# BMD_RevB_B3_FPGA.net
KiCad netlist of a schematic drawn in Altium Designer
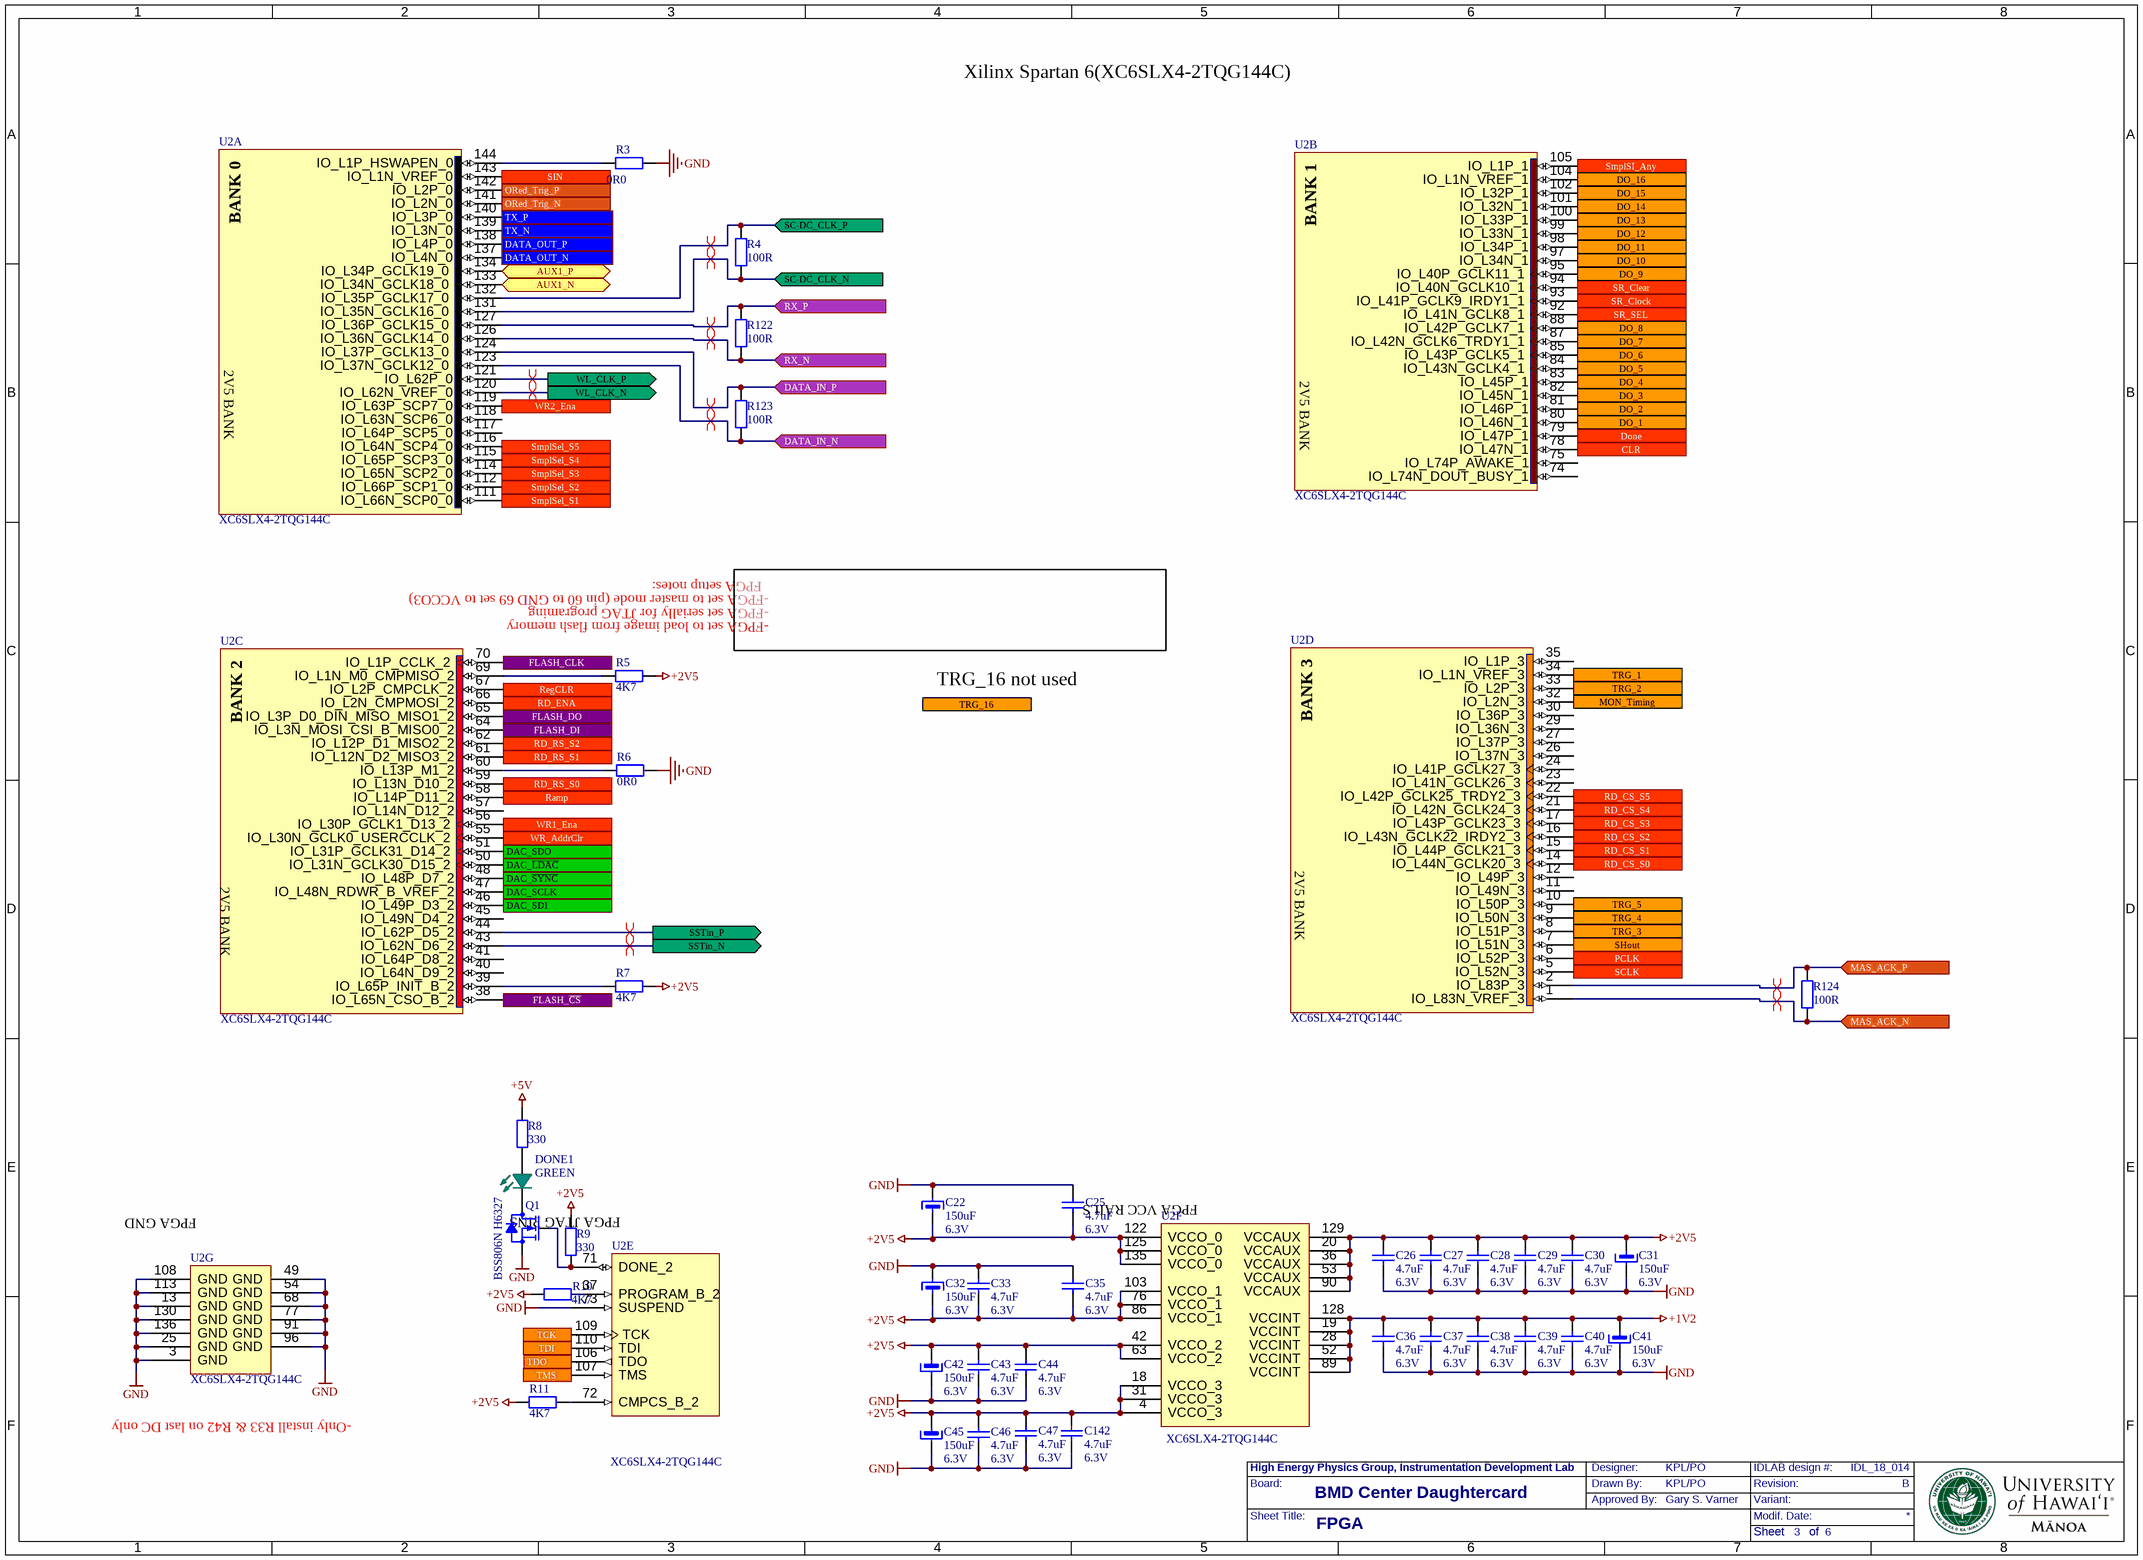
[diagram p0: BMD_RevB_B3_FPGA.SchDoc]

(export (version "E")
  (design (tool "Eeschema 10.0.6"))
  (components
    (comp (ref "C22")
      (value "150uF")
      (footprint "CTC-B3528-21")
      (description "150µF Molded Tantalum Capacitors 6.3V 1411")
      (fields (field (name "MANUFACTURER") "AVX") (field (name "VOLTAGE") "6.3V"))
      (libsource (lib "") (part "CAPT3528_150U6V3R0.5_1"))
    )
    (comp (ref "C25")
      (value "4.7uF")
      (footprint "CC0402N1R")
      (description "4.7µF ±10% 6.3V X7R Ceramic Capacitor")
      (fields
        (field (name "MANUFACTURER") "Samsung Electro-Mechanics America, Inc.")
        (field (name "VOLTAGE RATING") "6.3V")
      )
      (libsource (lib "BMD") (part "CAPCC0402_4.7uF_6.3V"))
    )
    (comp (ref "C26")
      (value "4.7uF")
      (footprint "CC0402N1R")
      (description "4.7µF ±10% 6.3V X7R Ceramic Capacitor")
      (fields
        (field (name "MANUFACTURER") "Samsung Electro-Mechanics America, Inc.")
        (field (name "VOLTAGE RATING") "6.3V")
      )
      (libsource (lib "BMD") (part "CAPCC0402_4.7uF_6.3V"))
    )
    (comp (ref "C27")
      (value "4.7uF")
      (footprint "CC0402N1R")
      (description "4.7µF ±10% 6.3V X7R Ceramic Capacitor")
      (fields
        (field (name "MANUFACTURER") "Samsung Electro-Mechanics America, Inc.")
        (field (name "VOLTAGE RATING") "6.3V")
      )
      (libsource (lib "BMD") (part "CAPCC0402_4.7uF_6.3V"))
    )
    (comp (ref "C28")
      (value "4.7uF")
      (footprint "CC0402N1R")
      (description "4.7µF ±10% 6.3V X7R Ceramic Capacitor")
      (fields
        (field (name "MANUFACTURER") "Samsung Electro-Mechanics America, Inc.")
        (field (name "VOLTAGE RATING") "6.3V")
      )
      (libsource (lib "BMD") (part "CAPCC0402_4.7uF_6.3V"))
    )
    (comp (ref "C29")
      (value "4.7uF")
      (footprint "CC0402N1R")
      (description "4.7µF ±10% 6.3V X7R Ceramic Capacitor")
      (fields
        (field (name "MANUFACTURER") "Samsung Electro-Mechanics America, Inc.")
        (field (name "VOLTAGE RATING") "6.3V")
      )
      (libsource (lib "BMD") (part "CAPCC0402_4.7uF_6.3V"))
    )
    (comp (ref "C30")
      (value "4.7uF")
      (footprint "CC0402N1R")
      (description "4.7µF ±10% 6.3V X7R Ceramic Capacitor")
      (fields
        (field (name "MANUFACTURER") "Samsung Electro-Mechanics America, Inc.")
        (field (name "VOLTAGE RATING") "6.3V")
      )
      (libsource (lib "BMD") (part "CAPCC0402_4.7uF_6.3V"))
    )
    (comp (ref "C31")
      (value "150uF")
      (footprint "CTC-B3528-21")
      (description "150µF Molded Tantalum Capacitors 6.3V 1411")
      (fields (field (name "MANUFACTURER") "AVX") (field (name "VOLTAGE") "6.3V"))
      (libsource (lib "BMD") (part "CAPT3528_150U6V3R0.5"))
    )
    (comp (ref "C32")
      (value "150uF")
      (footprint "CTC-B3528-21")
      (description "150µF Molded Tantalum Capacitors 6.3V 1411")
      (fields (field (name "MANUFACTURER") "AVX") (field (name "VOLTAGE") "6.3V"))
      (libsource (lib "") (part "CAPT3528_150U6V3R0.5_1"))
    )
    (comp (ref "C33")
      (value "4.7uF")
      (footprint "CC0402N1R")
      (description "4.7µF ±10% 6.3V X7R Ceramic Capacitor")
      (fields
        (field (name "MANUFACTURER") "Samsung Electro-Mechanics America, Inc.")
        (field (name "VOLTAGE RATING") "6.3V")
      )
      (libsource (lib "BMD") (part "CAPCC0402_4.7uF_6.3V"))
    )
    (comp (ref "C35")
      (value "4.7uF")
      (footprint "CC0402N1R")
      (description "4.7µF ±10% 6.3V X7R Ceramic Capacitor")
      (fields
        (field (name "MANUFACTURER") "Samsung Electro-Mechanics America, Inc.")
        (field (name "VOLTAGE RATING") "6.3V")
      )
      (libsource (lib "BMD") (part "CAPCC0402_4.7uF_6.3V"))
    )
    (comp (ref "C36")
      (value "4.7uF")
      (footprint "CC0402N1R")
      (description "4.7µF ±10% 6.3V X7R Ceramic Capacitor")
      (fields
        (field (name "MANUFACTURER") "Samsung Electro-Mechanics America, Inc.")
        (field (name "VOLTAGE RATING") "6.3V")
      )
      (libsource (lib "BMD") (part "CAPCC0402_4.7uF_6.3V"))
    )
    (comp (ref "C37")
      (value "4.7uF")
      (footprint "CC0402N1R")
      (description "4.7µF ±10% 6.3V X7R Ceramic Capacitor")
      (fields
        (field (name "MANUFACTURER") "Samsung Electro-Mechanics America, Inc.")
        (field (name "VOLTAGE RATING") "6.3V")
      )
      (libsource (lib "BMD") (part "CAPCC0402_4.7uF_6.3V"))
    )
    (comp (ref "C38")
      (value "4.7uF")
      (footprint "CC0402N1R")
      (description "4.7µF ±10% 6.3V X7R Ceramic Capacitor")
      (fields
        (field (name "MANUFACTURER") "Samsung Electro-Mechanics America, Inc.")
        (field (name "VOLTAGE RATING") "6.3V")
      )
      (libsource (lib "BMD") (part "CAPCC0402_4.7uF_6.3V"))
    )
    (comp (ref "C39")
      (value "4.7uF")
      (footprint "CC0402N1R")
      (description "4.7µF ±10% 6.3V X7R Ceramic Capacitor")
      (fields
        (field (name "MANUFACTURER") "Samsung Electro-Mechanics America, Inc.")
        (field (name "VOLTAGE RATING") "6.3V")
      )
      (libsource (lib "BMD") (part "CAPCC0402_4.7uF_6.3V"))
    )
    (comp (ref "C40")
      (value "4.7uF")
      (footprint "CC0402N1R")
      (description "4.7µF ±10% 6.3V X7R Ceramic Capacitor")
      (fields
        (field (name "MANUFACTURER") "Samsung Electro-Mechanics America, Inc.")
        (field (name "VOLTAGE RATING") "6.3V")
      )
      (libsource (lib "BMD") (part "CAPCC0402_4.7uF_6.3V"))
    )
    (comp (ref "C41")
      (value "150uF")
      (footprint "CTC-B3528-21")
      (description "150µF Molded Tantalum Capacitors 6.3V 1411")
      (fields (field (name "MANUFACTURER") "AVX") (field (name "VOLTAGE") "6.3V"))
      (libsource (lib "BMD") (part "CAPT3528_150U6V3R0.5"))
    )
    (comp (ref "C42")
      (value "150uF")
      (footprint "CTC-B3528-21")
      (description "150µF Molded Tantalum Capacitors 6.3V 1411")
      (fields (field (name "MANUFACTURER") "AVX") (field (name "VOLTAGE") "6.3V"))
      (libsource (lib "BMD") (part "CAPT3528_150U6V3R0.5"))
    )
    (comp (ref "C43")
      (value "4.7uF")
      (footprint "CC0402N1R")
      (description "4.7µF ±10% 6.3V X7R Ceramic Capacitor")
      (fields
        (field (name "MANUFACTURER") "Samsung Electro-Mechanics America, Inc.")
        (field (name "VOLTAGE RATING") "6.3V")
      )
      (libsource (lib "BMD") (part "CAPCC0402_4.7uF_6.3V"))
    )
    (comp (ref "C44")
      (value "4.7uF")
      (footprint "CC0402N1R")
      (description "4.7µF ±10% 6.3V X7R Ceramic Capacitor")
      (fields
        (field (name "MANUFACTURER") "Samsung Electro-Mechanics America, Inc.")
        (field (name "VOLTAGE RATING") "6.3V")
      )
      (libsource (lib "BMD") (part "CAPCC0402_4.7uF_6.3V"))
    )
    (comp (ref "C45")
      (value "150uF")
      (footprint "CTC-B3528-21")
      (description "150µF Molded Tantalum Capacitors 6.3V 1411")
      (fields (field (name "MANUFACTURER") "AVX") (field (name "VOLTAGE") "6.3V"))
      (libsource (lib "BMD") (part "CAPT3528_150U6V3R0.5"))
    )
    (comp (ref "C46")
      (value "4.7uF")
      (footprint "CC0402N1R")
      (description "4.7µF ±10% 6.3V X7R Ceramic Capacitor")
      (fields
        (field (name "MANUFACTURER") "Samsung Electro-Mechanics America, Inc.")
        (field (name "VOLTAGE RATING") "6.3V")
      )
      (libsource (lib "BMD") (part "CAPCC0402_4.7uF_6.3V"))
    )
    (comp (ref "C47")
      (value "4.7uF")
      (footprint "CC0402N1R")
      (description "4.7µF ±10% 6.3V X7R Ceramic Capacitor")
      (fields
        (field (name "MANUFACTURER") "Samsung Electro-Mechanics America, Inc.")
        (field (name "VOLTAGE RATING") "6.3V")
      )
      (libsource (lib "BMD") (part "CAPCC0402_4.7uF_6.3V"))
    )
    (comp (ref "C142")
      (value "4.7uF")
      (footprint "CC0402N1R")
      (description "4.7µF ±10% 6.3V X7R Ceramic Capacitor")
      (fields
        (field (name "MANUFACTURER") "Samsung Electro-Mechanics America, Inc.")
        (field (name "VOLTAGE RATING") "6.3V")
      )
      (libsource (lib "BMD") (part "CAPCC0402_4.7uF_6.3V"))
    )
    (comp (ref "DONE1")
      (value "GREEN")
      (footprint "LED0603VG")
      (description "Green 572nm LED Indication - Discrete 2.2V 0603")
      (fields (field (name "MANUFACTURER") "Rohm Semiconductor"))
      (libsource (lib "BMD") (part "LED-GREEN0603H"))
    )
    (comp (ref "Q1")
      (value "BSS806N H6327")
      (footprint "SOT23-1")
      (description "MOSFET N-CH 20V 2.3A SOT23")
      (fields (field (name "MANUFACTURER") "Infineon Technologies"))
      (libsource (lib "BMD") (part "MOSFET_N_Channel"))
    )
    (comp (ref "R3")
      (value "0R0")
      (footprint "RC0402N1R")
      (description "Chip Resistor 0402 62.5mW 1% 100ppm")
      (fields (field (name "MANUFACTURER") "Panasonic"))
      (libsource (lib "BMD") (part "RES0402-0R-1%100PPM"))
    )
    (comp (ref "R4")
      (value "100R")
      (footprint "RC0402N1R")
      (description "RES SMD 100 OHM 1% 1/10W 0402")
      (fields (field (name "MANUFACTURER") "Panasonic"))
      (libsource (lib "BMD") (part "RES0402-100R-1%100PPM"))
    )
    (comp (ref "R5")
      (value "4K7")
      (footprint "RC0402N1R")
      (description "RES SMD 4.7K OHM 1% 1/10W 0402")
      (fields (field (name "MANUFACTURER") "Panasonic"))
      (libsource (lib "") (part "RES0402-4.7K-1%100PPM_1"))
    )
    (comp (ref "R6")
      (value "0R0")
      (footprint "RC0402N1R")
      (description "Chip Resistor 0402 62.5mW 1% 100ppm")
      (fields (field (name "MANUFACTURER") "Panasonic"))
      (libsource (lib "BMD") (part "RES0402-0R-1%100PPM"))
    )
    (comp (ref "R7")
      (value "4K7")
      (footprint "RC0402N1R")
      (description "RES SMD 4.7K OHM 1% 1/10W 0402")
      (fields (field (name "MANUFACTURER") "Panasonic"))
      (libsource (lib "") (part "RES0402-4.7K-1%100PPM_1"))
    )
    (comp (ref "R8")
      (value "330")
      (footprint "RC0402N1R")
      (description "RES SMD 330 OHM 0.1% 1/16W 0402")
      (fields (field (name "MANUFACTURER") "Panasonic Electronic Components"))
      (libsource (lib "") (part "RES0402_330_1%_1"))
    )
    (comp (ref "R9")
      (value "330")
      (footprint "RC0402N1R")
      (description "RES SMD 330 OHM 0.1% 1/16W 0402")
      (fields (field (name "MANUFACTURER") "Panasonic Electronic Components"))
      (libsource (lib "BMD") (part "RES0402_330_1%"))
    )
    (comp (ref "R10")
      (value "4K7")
      (footprint "RC0402N1R")
      (description "RES SMD 4.7K OHM 1% 1/10W 0402")
      (fields (field (name "MANUFACTURER") "Panasonic"))
      (libsource (lib "BMD") (part "RES0402-4.7K-1%100PPM"))
    )
    (comp (ref "R11")
      (value "4K7")
      (footprint "RC0402N1R")
      (description "RES SMD 4.7K OHM 1% 1/10W 0402")
      (fields (field (name "MANUFACTURER") "Panasonic"))
      (libsource (lib "") (part "RES0402-4.7K-1%100PPM_1"))
    )
    (comp (ref "R122")
      (value "100R")
      (footprint "RC0402N1R")
      (description "RES SMD 100 OHM 1% 1/10W 0402")
      (fields (field (name "MANUFACTURER") "Panasonic"))
      (libsource (lib "BMD") (part "RES0402-100R-1%100PPM"))
    )
    (comp (ref "R123")
      (value "100R")
      (footprint "RC0402N1R")
      (description "RES SMD 100 OHM 1% 1/10W 0402")
      (fields (field (name "MANUFACTURER") "Panasonic"))
      (libsource (lib "BMD") (part "RES0402-100R-1%100PPM"))
    )
    (comp (ref "R124")
      (value "100R")
      (footprint "RC0402N1R")
      (description "RES SMD 100 OHM 1% 1/10W 0402")
      (fields (field (name "MANUFACTURER") "Panasonic"))
      (libsource (lib "BMD") (part "RES0402-100R-1%100PPM"))
    )
    (comp (ref "U2")
      (value "XC6SLX4-2TQG144C")
      (footprint "TQG144_N")
      (fields (field (name "MANUFACTURER") "Xillinx Inc") (field (name "PUBLISHER") "Altium Limited"))
      (libsource (lib "BMD") (part "SPARTAN_6"))
    )
  )
  (nets
    (net (code "1") (name "+1V2") (class "Default")
      (node (ref "C36") (pin "2") (pinfunction "2_2") (pintype "passive"))
      (node (ref "C37") (pin "2") (pinfunction "2_2") (pintype "passive"))
      (node (ref "C38") (pin "2") (pinfunction "2_2") (pintype "passive"))
      (node (ref "C39") (pin "2") (pinfunction "2_2") (pintype "passive"))
      (node (ref "C40") (pin "2") (pinfunction "2_2") (pintype "passive"))
      (node (ref "C41") (pin "1") (pinfunction "1_1") (pintype "passive"))
      (node (ref "U2") (pin "128") (pinfunction "VCCINT_128") (pintype "power_in"))
      (node (ref "U2") (pin "19") (pinfunction "VCCINT_19") (pintype "power_in"))
      (node (ref "U2") (pin "28") (pinfunction "VCCINT_28") (pintype "power_in"))
      (node (ref "U2") (pin "52") (pinfunction "VCCINT_52") (pintype "power_in"))
      (node (ref "U2") (pin "89") (pinfunction "VCCINT_89") (pintype "power_in"))
    )
    (net (code "2") (name "+2V5") (class "Default")
      (node (ref "C142") (pin "2") (pinfunction "2_2") (pintype "passive"))
      (node (ref "C22") (pin "1") (pinfunction "1_1") (pintype "passive"))
      (node (ref "C25") (pin "1") (pinfunction "1_1") (pintype "passive"))
      (node (ref "C26") (pin "2") (pinfunction "2_2") (pintype "passive"))
      (node (ref "C27") (pin "2") (pinfunction "2_2") (pintype "passive"))
      (node (ref "C28") (pin "2") (pinfunction "2_2") (pintype "passive"))
      (node (ref "C29") (pin "2") (pinfunction "2_2") (pintype "passive"))
      (node (ref "C30") (pin "2") (pinfunction "2_2") (pintype "passive"))
      (node (ref "C31") (pin "1") (pinfunction "1_1") (pintype "passive"))
      (node (ref "C32") (pin "1") (pinfunction "1_1") (pintype "passive"))
      (node (ref "C33") (pin "1") (pinfunction "1_1") (pintype "passive"))
      (node (ref "C35") (pin "1") (pinfunction "1_1") (pintype "passive"))
      (node (ref "C42") (pin "1") (pinfunction "1_1") (pintype "passive"))
      (node (ref "C43") (pin "2") (pinfunction "2_2") (pintype "passive"))
      (node (ref "C44") (pin "2") (pinfunction "2_2") (pintype "passive"))
      (node (ref "C45") (pin "1") (pinfunction "1_1") (pintype "passive"))
      (node (ref "C46") (pin "2") (pinfunction "2_2") (pintype "passive"))
      (node (ref "C47") (pin "2") (pinfunction "2_2") (pintype "passive"))
      (node (ref "R10") (pin "2") (pinfunction "2_2") (pintype "passive"))
      (node (ref "R11") (pin "1") (pinfunction "1_1") (pintype "passive"))
      (node (ref "R5") (pin "2") (pinfunction "2_2") (pintype "passive"))
      (node (ref "R7") (pin "2") (pinfunction "2_2") (pintype "passive"))
      (node (ref "R9") (pin "1") (pinfunction "1_1") (pintype "passive"))
      (node (ref "U2") (pin "103") (pinfunction "VCCO_1_103") (pintype "power_in"))
      (node (ref "U2") (pin "122") (pinfunction "VCCO_0_122") (pintype "power_in"))
      (node (ref "U2") (pin "125") (pinfunction "VCCO_0_125") (pintype "power_in"))
      (node (ref "U2") (pin "129") (pinfunction "VCCAUX_129") (pintype "power_in"))
      (node (ref "U2") (pin "135") (pinfunction "VCCO_0_135") (pintype "power_in"))
      (node (ref "U2") (pin "18") (pinfunction "VCCO_3_18") (pintype "power_in"))
      (node (ref "U2") (pin "20") (pinfunction "VCCAUX_20") (pintype "power_in"))
      (node (ref "U2") (pin "31") (pinfunction "VCCO_3_31") (pintype "power_in"))
      (node (ref "U2") (pin "36") (pinfunction "VCCAUX_36") (pintype "power_in"))
      (node (ref "U2") (pin "4") (pinfunction "VCCO_3_4") (pintype "power_in"))
      (node (ref "U2") (pin "42") (pinfunction "VCCO_2_42") (pintype "power_in"))
      (node (ref "U2") (pin "53") (pinfunction "VCCAUX_53") (pintype "power_in"))
      (node (ref "U2") (pin "63") (pinfunction "VCCO_2_63") (pintype "power_in"))
      (node (ref "U2") (pin "76") (pinfunction "VCCO_1_76") (pintype "power_in"))
      (node (ref "U2") (pin "86") (pinfunction "VCCO_1_86") (pintype "power_in"))
      (node (ref "U2") (pin "90") (pinfunction "VCCAUX_90") (pintype "power_in"))
    )
    (net (code "3") (name "+5V") (class "Default")
      (node (ref "R8") (pin "1") (pinfunction "1_1") (pintype "passive"))
    )
    (net (code "4") (name "/AUX1_N") (class "Default")
      (node (ref "U2") (pin "133") (pinfunction "IO_L34N_GCLK18_0_133") (pintype "bidirectional"))
    )
    (net (code "5") (name "/AUX1_P") (class "Default")
      (node (ref "U2") (pin "134") (pinfunction "IO_L34P_GCLK19_0_134") (pintype "bidirectional"))
    )
    (net (code "6") (name "/CLR") (class "Default")
      (node (ref "U2") (pin "78") (pinfunction "IO_L47N_1_78") (pintype "bidirectional"))
    )
    (net (code "7") (name "/DAC_SCLK") (class "Default")
      (node (ref "U2") (pin "47") (pinfunction "IO_L48N_RDWR_B_VREF_2_47") (pintype "bidirectional"))
    )
    (net (code "8") (name "/DAC_SDI") (class "Default")
      (node (ref "U2") (pin "46") (pinfunction "IO_L49P_D3_2_46") (pintype "bidirectional"))
    )
    (net (code "9") (name "/DAC_SDO") (class "Default")
      (node (ref "U2") (pin "51") (pinfunction "IO_L31P_GCLK31_D14_2_51") (pintype "bidirectional"))
    )
    (net (code "10") (name "/DAC_~{LDAC}") (class "Default")
      (node (ref "U2") (pin "50") (pinfunction "IO_L31N_GCLK30_D15_2_50") (pintype "bidirectional"))
    )
    (net (code "11") (name "/DAC_~{SYNC}") (class "Default")
      (node (ref "U2") (pin "48") (pinfunction "IO_L48P_D7_2_48") (pintype "bidirectional"))
    )
    (net (code "12") (name "/DATA_IN_N") (class "Default")
      (node (ref "R123") (pin "1") (pinfunction "1_1") (pintype "passive"))
      (node (ref "U2") (pin "123") (pinfunction "IO_L37N_GCLK12_0_123") (pintype "bidirectional"))
    )
    (net (code "13") (name "/DATA_IN_P") (class "Default")
      (node (ref "R123") (pin "2") (pinfunction "2_2") (pintype "passive"))
      (node (ref "U2") (pin "124") (pinfunction "IO_L37P_GCLK13_0_124") (pintype "bidirectional"))
    )
    (net (code "14") (name "/DATA_OUT_N") (class "Default")
      (node (ref "U2") (pin "137") (pinfunction "IO_L4N_0_137") (pintype "bidirectional"))
    )
    (net (code "15") (name "/DATA_OUT_P") (class "Default")
      (node (ref "U2") (pin "138") (pinfunction "IO_L4P_0_138") (pintype "bidirectional"))
    )
    (net (code "16") (name "/DO_1") (class "Default")
      (node (ref "U2") (pin "80") (pinfunction "IO_L46N_1_80") (pintype "bidirectional"))
    )
    (net (code "17") (name "/DO_2") (class "Default")
      (node (ref "U2") (pin "81") (pinfunction "IO_L46P_1_81") (pintype "bidirectional"))
    )
    (net (code "18") (name "/DO_3") (class "Default")
      (node (ref "U2") (pin "82") (pinfunction "IO_L45N_1_82") (pintype "bidirectional"))
    )
    (net (code "19") (name "/DO_4") (class "Default")
      (node (ref "U2") (pin "83") (pinfunction "IO_L45P_1_83") (pintype "bidirectional"))
    )
    (net (code "20") (name "/DO_5") (class "Default")
      (node (ref "U2") (pin "84") (pinfunction "IO_L43N_GCLK4_1_84") (pintype "bidirectional"))
    )
    (net (code "21") (name "/DO_6") (class "Default")
      (node (ref "U2") (pin "85") (pinfunction "IO_L43P_GCLK5_1_85") (pintype "bidirectional"))
    )
    (net (code "22") (name "/DO_7") (class "Default")
      (node (ref "U2") (pin "87") (pinfunction "IO_L42N_GCLK6_TRDY1_1_87") (pintype "bidirectional"))
    )
    (net (code "23") (name "/DO_8") (class "Default")
      (node (ref "U2") (pin "88") (pinfunction "IO_L42P_GCLK7_1_88") (pintype "bidirectional"))
    )
    (net (code "24") (name "/DO_9") (class "Default")
      (node (ref "U2") (pin "95") (pinfunction "IO_L40P_GCLK11_1_95") (pintype "bidirectional"))
    )
    (net (code "25") (name "/DO_10") (class "Default")
      (node (ref "U2") (pin "97") (pinfunction "IO_L34N_1_97") (pintype "bidirectional"))
    )
    (net (code "26") (name "/DO_11") (class "Default")
      (node (ref "U2") (pin "98") (pinfunction "IO_L34P_1_98") (pintype "bidirectional"))
    )
    (net (code "27") (name "/DO_12") (class "Default")
      (node (ref "U2") (pin "99") (pinfunction "IO_L33N_1_99") (pintype "bidirectional"))
    )
    (net (code "28") (name "/DO_13") (class "Default")
      (node (ref "U2") (pin "100") (pinfunction "IO_L33P_1_100") (pintype "bidirectional"))
    )
    (net (code "29") (name "/DO_14") (class "Default")
      (node (ref "U2") (pin "101") (pinfunction "IO_L32N_1_101") (pintype "bidirectional"))
    )
    (net (code "30") (name "/DO_15") (class "Default")
      (node (ref "U2") (pin "102") (pinfunction "IO_L32P_1_102") (pintype "bidirectional"))
    )
    (net (code "31") (name "/DO_16") (class "Default")
      (node (ref "U2") (pin "104") (pinfunction "IO_L1N_VREF_1_104") (pintype "bidirectional"))
    )
    (net (code "32") (name "/Done") (class "Default")
      (node (ref "U2") (pin "79") (pinfunction "IO_L47P_1_79") (pintype "bidirectional"))
    )
    (net (code "33") (name "/FLASH_CLK") (class "Default")
      (node (ref "U2") (pin "70") (pinfunction "IO_L1P_CCLK_2_70") (pintype "bidirectional"))
    )
    (net (code "34") (name "/FLASH_DI") (class "Default")
      (node (ref "U2") (pin "64") (pinfunction "IO_L3N_MOSI_CSI_B_MISO0_2_64") (pintype "bidirectional"))
    )
    (net (code "35") (name "/FLASH_DO") (class "Default")
      (node (ref "U2") (pin "65") (pinfunction "IO_L3P_D0_DIN_MISO_MISO1_2_65") (pintype "bidirectional"))
    )
    (net (code "36") (name "/FLASH_~{CS}") (class "Default")
      (node (ref "U2") (pin "38") (pinfunction "IO_L65N_CSO_B_2_38") (pintype "bidirectional"))
    )
    (net (code "37") (name "/MAS_ACK_N") (class "Default")
      (node (ref "R124") (pin "1") (pinfunction "1_1") (pintype "passive"))
      (node (ref "U2") (pin "1") (pinfunction "IO_L83N_VREF_3_1") (pintype "bidirectional"))
    )
    (net (code "38") (name "/MAS_ACK_P") (class "Default")
      (node (ref "R124") (pin "2") (pinfunction "2_2") (pintype "passive"))
      (node (ref "U2") (pin "2") (pinfunction "IO_L83P_3_2") (pintype "bidirectional"))
    )
    (net (code "39") (name "/MON_Timing") (class "Default")
      (node (ref "U2") (pin "32") (pinfunction "IO_L2N_3_32") (pintype "bidirectional"))
    )
    (net (code "40") (name "/ORed_Trig_N") (class "Default")
      (node (ref "U2") (pin "141") (pinfunction "IO_L2N_0_141") (pintype "bidirectional"))
    )
    (net (code "41") (name "/ORed_Trig_P") (class "Default")
      (node (ref "U2") (pin "142") (pinfunction "IO_L2P_0_142") (pintype "bidirectional"))
    )
    (net (code "42") (name "/PCLK") (class "Default")
      (node (ref "U2") (pin "6") (pinfunction "IO_L52P_3_6") (pintype "bidirectional"))
    )
    (net (code "43") (name "/RD_CS_S0") (class "Default")
      (node (ref "U2") (pin "14") (pinfunction "IO_L44N_GCLK20_3_14") (pintype "bidirectional"))
    )
    (net (code "44") (name "/RD_CS_S1") (class "Default")
      (node (ref "U2") (pin "15") (pinfunction "IO_L44P_GCLK21_3_15") (pintype "bidirectional"))
    )
    (net (code "45") (name "/RD_CS_S2") (class "Default")
      (node (ref "U2") (pin "16") (pinfunction "IO_L43N_GCLK22_IRDY2_3_16") (pintype "bidirectional"))
    )
    (net (code "46") (name "/RD_CS_S3") (class "Default")
      (node (ref "U2") (pin "17") (pinfunction "IO_L43P_GCLK23_3_17") (pintype "bidirectional"))
    )
    (net (code "47") (name "/RD_CS_S4") (class "Default")
      (node (ref "U2") (pin "21") (pinfunction "IO_L42N_GCLK24_3_21") (pintype "bidirectional"))
    )
    (net (code "48") (name "/RD_CS_S5") (class "Default")
      (node (ref "U2") (pin "22") (pinfunction "IO_L42P_GCLK25_TRDY2_3_22") (pintype "bidirectional"))
    )
    (net (code "49") (name "/RD_ENA") (class "Default")
      (node (ref "U2") (pin "66") (pinfunction "IO_L2N_CMPMOSI_2_66") (pintype "bidirectional"))
    )
    (net (code "50") (name "/RD_RS_S0") (class "Default")
      (node (ref "U2") (pin "59") (pinfunction "IO_L13N_D10_2_59") (pintype "bidirectional"))
    )
    (net (code "51") (name "/RD_RS_S1") (class "Default")
      (node (ref "U2") (pin "61") (pinfunction "IO_L12N_D2_MISO3_2_61") (pintype "bidirectional"))
    )
    (net (code "52") (name "/RD_RS_S2") (class "Default")
      (node (ref "U2") (pin "62") (pinfunction "IO_L12P_D1_MISO2_2_62") (pintype "bidirectional"))
    )
    (net (code "53") (name "/RX_N") (class "Default")
      (node (ref "R122") (pin "1") (pinfunction "1_1") (pintype "passive"))
      (node (ref "U2") (pin "126") (pinfunction "IO_L36N_GCLK14_0_126") (pintype "bidirectional"))
    )
    (net (code "54") (name "/RX_P") (class "Default")
      (node (ref "R122") (pin "2") (pinfunction "2_2") (pintype "passive"))
      (node (ref "U2") (pin "127") (pinfunction "IO_L36P_GCLK15_0_127") (pintype "bidirectional"))
    )
    (net (code "55") (name "/Ramp") (class "Default")
      (node (ref "U2") (pin "58") (pinfunction "IO_L14P_D11_2_58") (pintype "bidirectional"))
    )
    (net (code "56") (name "/RegCLR") (class "Default")
      (node (ref "U2") (pin "67") (pinfunction "IO_L2P_CMPCLK_2_67") (pintype "bidirectional"))
    )
    (net (code "57") (name "/SC-DC_CLK_N") (class "Default")
      (node (ref "R4") (pin "1") (pinfunction "1_1") (pintype "passive"))
      (node (ref "U2") (pin "131") (pinfunction "IO_L35N_GCLK16_0_131") (pintype "bidirectional"))
    )
    (net (code "58") (name "/SC-DC_CLK_P") (class "Default")
      (node (ref "R4") (pin "2") (pinfunction "2_2") (pintype "passive"))
      (node (ref "U2") (pin "132") (pinfunction "IO_L35P_GCLK17_0_132") (pintype "bidirectional"))
    )
    (net (code "59") (name "/SCLK") (class "Default")
      (node (ref "U2") (pin "5") (pinfunction "IO_L52N_3_5") (pintype "bidirectional"))
    )
    (net (code "60") (name "/SHout") (class "Default")
      (node (ref "U2") (pin "7") (pinfunction "IO_L51N_3_7") (pintype "bidirectional"))
    )
    (net (code "61") (name "/SIN") (class "Default")
      (node (ref "U2") (pin "143") (pinfunction "IO_L1N_VREF_0_143") (pintype "bidirectional"))
    )
    (net (code "62") (name "/SR_Clear") (class "Default")
      (node (ref "U2") (pin "94") (pinfunction "IO_L40N_GCLK10_1_94") (pintype "bidirectional"))
    )
    (net (code "63") (name "/SR_Clock") (class "Default")
      (node (ref "U2") (pin "93") (pinfunction "IO_L41P_GCLK9_IRDY1_1_93") (pintype "bidirectional"))
    )
    (net (code "64") (name "/SR_SEL") (class "Default")
      (node (ref "U2") (pin "92") (pinfunction "IO_L41N_GCLK8_1_92") (pintype "bidirectional"))
    )
    (net (code "65") (name "/SSTin_N") (class "Default")
      (node (ref "U2") (pin "43") (pinfunction "IO_L62N_D6_2_43") (pintype "bidirectional"))
    )
    (net (code "66") (name "/SSTin_P") (class "Default")
      (node (ref "U2") (pin "44") (pinfunction "IO_L62P_D5_2_44") (pintype "bidirectional"))
    )
    (net (code "67") (name "/SmplSI_Any") (class "Default")
      (node (ref "U2") (pin "105") (pinfunction "IO_L1P_1_105") (pintype "bidirectional"))
    )
    (net (code "68") (name "/SmplSel_S1") (class "Default")
      (node (ref "U2") (pin "111") (pinfunction "IO_L66N_SCP0_0_111") (pintype "bidirectional"))
    )
    (net (code "69") (name "/SmplSel_S2") (class "Default")
      (node (ref "U2") (pin "112") (pinfunction "IO_L66P_SCP1_0_112") (pintype "bidirectional"))
    )
    (net (code "70") (name "/SmplSel_S3") (class "Default")
      (node (ref "U2") (pin "114") (pinfunction "IO_L65N_SCP2_0_114") (pintype "bidirectional"))
    )
    (net (code "71") (name "/SmplSel_S4") (class "Default")
      (node (ref "U2") (pin "115") (pinfunction "IO_L65P_SCP3_0_115") (pintype "bidirectional"))
    )
    (net (code "72") (name "/SmplSel_S5") (class "Default")
      (node (ref "U2") (pin "116") (pinfunction "IO_L64N_SCP4_0_116") (pintype "bidirectional"))
    )
    (net (code "73") (name "/TCK") (class "Default")
      (node (ref "U2") (pin "109") (pinfunction "TCK_109") (pintype "input"))
    )
    (net (code "74") (name "/TDI") (class "Default")
      (node (ref "U2") (pin "110") (pinfunction "TDI_110") (pintype "input"))
    )
    (net (code "75") (name "/TDO") (class "Default")
      (node (ref "U2") (pin "106") (pinfunction "TDO_106") (pintype "output"))
    )
    (net (code "76") (name "/TMS") (class "Default")
      (node (ref "U2") (pin "107") (pinfunction "TMS_107") (pintype "input"))
    )
    (net (code "77") (name "/TRG_1") (class "Default")
      (node (ref "U2") (pin "34") (pinfunction "IO_L1N_VREF_3_34") (pintype "bidirectional"))
    )
    (net (code "78") (name "/TRG_2") (class "Default")
      (node (ref "U2") (pin "33") (pinfunction "IO_L2P_3_33") (pintype "bidirectional"))
    )
    (net (code "79") (name "/TRG_3") (class "Default")
      (node (ref "U2") (pin "8") (pinfunction "IO_L51P_3_8") (pintype "bidirectional"))
    )
    (net (code "80") (name "/TRG_4") (class "Default")
      (node (ref "U2") (pin "9") (pinfunction "IO_L50N_3_9") (pintype "bidirectional"))
    )
    (net (code "81") (name "/TRG_5") (class "Default")
      (node (ref "U2") (pin "10") (pinfunction "IO_L50P_3_10") (pintype "bidirectional"))
    )
    (net (code "83") (name "/TX_N") (class "Default")
      (node (ref "U2") (pin "139") (pinfunction "IO_L3N_0_139") (pintype "bidirectional"))
    )
    (net (code "84") (name "/TX_P") (class "Default")
      (node (ref "U2") (pin "140") (pinfunction "IO_L3P_0_140") (pintype "bidirectional"))
    )
    (net (code "85") (name "/WL_CLK_N") (class "Default")
      (node (ref "U2") (pin "120") (pinfunction "IO_L62N_VREF_0_120") (pintype "bidirectional"))
    )
    (net (code "86") (name "/WL_CLK_P") (class "Default")
      (node (ref "U2") (pin "121") (pinfunction "IO_L62P_0_121") (pintype "bidirectional"))
    )
    (net (code "87") (name "/WR1_Ena") (class "Default")
      (node (ref "U2") (pin "56") (pinfunction "IO_L30P_GCLK1_D13_2_56") (pintype "bidirectional"))
    )
    (net (code "88") (name "/WR2_Ena") (class "Default")
      (node (ref "U2") (pin "119") (pinfunction "IO_L63P_SCP7_0_119") (pintype "bidirectional"))
    )
    (net (code "89") (name "/WR_AddrClr") (class "Default")
      (node (ref "U2") (pin "55") (pinfunction "IO_L30N_GCLK0_USERCCLK_2_55") (pintype "bidirectional"))
    )
    (net (code "90") (name "GND") (class "Default")
      (node (ref "C142") (pin "1") (pinfunction "1_1") (pintype "passive"))
      (node (ref "C22") (pin "2") (pinfunction "2_2") (pintype "passive"))
      (node (ref "C25") (pin "2") (pinfunction "2_2") (pintype "passive"))
      (node (ref "C26") (pin "1") (pinfunction "1_1") (pintype "passive"))
      (node (ref "C27") (pin "1") (pinfunction "1_1") (pintype "passive"))
      (node (ref "C28") (pin "1") (pinfunction "1_1") (pintype "passive"))
      (node (ref "C29") (pin "1") (pinfunction "1_1") (pintype "passive"))
      (node (ref "C30") (pin "1") (pinfunction "1_1") (pintype "passive"))
      (node (ref "C31") (pin "2") (pinfunction "2_2") (pintype "passive"))
      (node (ref "C32") (pin "2") (pinfunction "2_2") (pintype "passive"))
      (node (ref "C33") (pin "2") (pinfunction "2_2") (pintype "passive"))
      (node (ref "C35") (pin "2") (pinfunction "2_2") (pintype "passive"))
      (node (ref "C36") (pin "1") (pinfunction "1_1") (pintype "passive"))
      (node (ref "C37") (pin "1") (pinfunction "1_1") (pintype "passive"))
      (node (ref "C38") (pin "1") (pinfunction "1_1") (pintype "passive"))
      (node (ref "C39") (pin "1") (pinfunction "1_1") (pintype "passive"))
      (node (ref "C40") (pin "1") (pinfunction "1_1") (pintype "passive"))
      (node (ref "C41") (pin "2") (pinfunction "2_2") (pintype "passive"))
      (node (ref "C42") (pin "2") (pinfunction "2_2") (pintype "passive"))
      (node (ref "C43") (pin "1") (pinfunction "1_1") (pintype "passive"))
      (node (ref "C44") (pin "1") (pinfunction "1_1") (pintype "passive"))
      (node (ref "C45") (pin "2") (pinfunction "2_2") (pintype "passive"))
      (node (ref "C46") (pin "1") (pinfunction "1_1") (pintype "passive"))
      (node (ref "C47") (pin "1") (pinfunction "1_1") (pintype "passive"))
      (node (ref "Q1") (pin "2") (pinfunction "S_2") (pintype "passive"))
      (node (ref "R3") (pin "2") (pinfunction "2_2") (pintype "passive"))
      (node (ref "R6") (pin "2") (pinfunction "2_2") (pintype "passive"))
      (node (ref "U2") (pin "108") (pinfunction "GND_108") (pintype "power_in"))
      (node (ref "U2") (pin "113") (pinfunction "GND_113") (pintype "power_in"))
      (node (ref "U2") (pin "13") (pinfunction "GND_13") (pintype "power_in"))
      (node (ref "U2") (pin "130") (pinfunction "GND_130") (pintype "power_in"))
      (node (ref "U2") (pin "136") (pinfunction "GND_136") (pintype "power_in"))
      (node (ref "U2") (pin "25") (pinfunction "GND_25") (pintype "power_in"))
      (node (ref "U2") (pin "3") (pinfunction "GND_3") (pintype "power_in"))
      (node (ref "U2") (pin "49") (pinfunction "GND_49") (pintype "power_in"))
      (node (ref "U2") (pin "54") (pinfunction "GND_54") (pintype "power_in"))
      (node (ref "U2") (pin "68") (pinfunction "GND_68") (pintype "power_in"))
      (node (ref "U2") (pin "73") (pinfunction "SUSPEND_73") (pintype "input"))
      (node (ref "U2") (pin "77") (pinfunction "GND_77") (pintype "power_in"))
      (node (ref "U2") (pin "91") (pinfunction "GND_91") (pintype "power_in"))
      (node (ref "U2") (pin "96") (pinfunction "GND_96") (pintype "power_in"))
    )
    (net (code "91") (name "Net-(DONE1-A)") (class "Default")
      (node (ref "DONE1") (pin "2") (pinfunction "A_2") (pintype "passive"))
      (node (ref "R8") (pin "2") (pinfunction "2_2") (pintype "passive"))
    )
    (net (code "92") (name "Net-(DONE1-C)") (class "Default")
      (node (ref "DONE1") (pin "1") (pinfunction "C_1") (pintype "passive"))
      (node (ref "Q1") (pin "3") (pinfunction "D_3") (pintype "passive"))
    )
    (net (code "93") (name "Net-(Q1-G)") (class "Default")
      (node (ref "Q1") (pin "1") (pinfunction "G_1") (pintype "passive"))
      (node (ref "R9") (pin "2") (pinfunction "2_2") (pintype "passive"))
      (node (ref "U2") (pin "71") (pinfunction "DONE_2_71") (pintype "bidirectional"))
    )
    (net (code "94") (name "Net-(U2A-IO_L1P_HSWAPEN_0)") (class "Default")
      (node (ref "R3") (pin "1") (pinfunction "1_1") (pintype "passive"))
      (node (ref "U2") (pin "144") (pinfunction "IO_L1P_HSWAPEN_0_144") (pintype "bidirectional"))
    )
    (net (code "95") (name "Net-(U2C-IO_L1N_M0_CMPMISO_2)") (class "Default")
      (node (ref "R5") (pin "1") (pinfunction "1_1") (pintype "passive"))
      (node (ref "U2") (pin "69") (pinfunction "IO_L1N_M0_CMPMISO_2_69") (pintype "bidirectional"))
    )
    (net (code "96") (name "Net-(U2C-IO_L13P_M1_2)") (class "Default")
      (node (ref "R6") (pin "1") (pinfunction "1_1") (pintype "passive"))
      (node (ref "U2") (pin "60") (pinfunction "IO_L13P_M1_2_60") (pintype "bidirectional"))
    )
    (net (code "97") (name "Net-(U2C-IO_L65P_INIT_B_2)") (class "Default")
      (node (ref "R7") (pin "1") (pinfunction "1_1") (pintype "passive"))
      (node (ref "U2") (pin "39") (pinfunction "IO_L65P_INIT_B_2_39") (pintype "bidirectional"))
    )
    (net (code "98") (name "Net-(U2E-CMPCS_B_2)") (class "Default")
      (node (ref "R11") (pin "2") (pinfunction "2_2") (pintype "passive"))
      (node (ref "U2") (pin "72") (pinfunction "CMPCS_B_2_72") (pintype "input"))
    )
    (net (code "99") (name "Net-(U2E-PROGRAM_B_2)") (class "Default")
      (node (ref "R10") (pin "1") (pinfunction "1_1") (pintype "passive"))
      (node (ref "U2") (pin "37") (pinfunction "PROGRAM_B_2_37") (pintype "input"))
    )
    (net (code "100") (name "unconnected-(U2A-IO_L63N_SCP6_0-Pad118)") (class "Default")
      (node (ref "U2") (pin "118") (pinfunction "IO_L63N_SCP6_0_118") (pintype "bidirectional"))
    )
    (net (code "101") (name "unconnected-(U2A-IO_L64P_SCP5_0-Pad117)") (class "Default")
      (node (ref "U2") (pin "117") (pinfunction "IO_L64P_SCP5_0_117") (pintype "bidirectional"))
    )
    (net (code "102") (name "unconnected-(U2B-IO_L74N_DOUT_BUSY_1-Pad74)") (class "Default")
      (node (ref "U2") (pin "74") (pinfunction "IO_L74N_DOUT_BUSY_1_74") (pintype "bidirectional"))
    )
    (net (code "103") (name "unconnected-(U2B-IO_L74P_AWAKE_1-Pad75)") (class "Default")
      (node (ref "U2") (pin "75") (pinfunction "IO_L74P_AWAKE_1_75") (pintype "bidirectional"))
    )
    (net (code "104") (name "unconnected-(U2C-IO_L14N_D12_2-Pad57)") (class "Default")
      (node (ref "U2") (pin "57") (pinfunction "IO_L14N_D12_2_57") (pintype "bidirectional"))
    )
    (net (code "105") (name "unconnected-(U2C-IO_L49N_D4_2-Pad45)") (class "Default")
      (node (ref "U2") (pin "45") (pinfunction "IO_L49N_D4_2_45") (pintype "bidirectional"))
    )
    (net (code "106") (name "unconnected-(U2C-IO_L64N_D9_2-Pad40)") (class "Default")
      (node (ref "U2") (pin "40") (pinfunction "IO_L64N_D9_2_40") (pintype "bidirectional"))
    )
    (net (code "107") (name "unconnected-(U2C-IO_L64P_D8_2-Pad41)") (class "Default")
      (node (ref "U2") (pin "41") (pinfunction "IO_L64P_D8_2_41") (pintype "bidirectional"))
    )
    (net (code "108") (name "unconnected-(U2D-IO_L1P_3-Pad35)") (class "Default")
      (node (ref "U2") (pin "35") (pinfunction "IO_L1P_3_35") (pintype "bidirectional"))
    )
    (net (code "109") (name "unconnected-(U2D-IO_L36N_3-Pad29)") (class "Default")
      (node (ref "U2") (pin "29") (pinfunction "IO_L36N_3_29") (pintype "bidirectional"))
    )
    (net (code "110") (name "unconnected-(U2D-IO_L36P_3-Pad30)") (class "Default")
      (node (ref "U2") (pin "30") (pinfunction "IO_L36P_3_30") (pintype "bidirectional"))
    )
    (net (code "111") (name "unconnected-(U2D-IO_L37N_3-Pad26)") (class "Default")
      (node (ref "U2") (pin "26") (pinfunction "IO_L37N_3_26") (pintype "bidirectional"))
    )
    (net (code "112") (name "unconnected-(U2D-IO_L37P_3-Pad27)") (class "Default")
      (node (ref "U2") (pin "27") (pinfunction "IO_L37P_3_27") (pintype "bidirectional"))
    )
    (net (code "113") (name "unconnected-(U2D-IO_L41N_GCLK26_3-Pad23)") (class "Default")
      (node (ref "U2") (pin "23") (pinfunction "IO_L41N_GCLK26_3_23") (pintype "bidirectional"))
    )
    (net (code "114") (name "unconnected-(U2D-IO_L41P_GCLK27_3-Pad24)") (class "Default")
      (node (ref "U2") (pin "24") (pinfunction "IO_L41P_GCLK27_3_24") (pintype "bidirectional"))
    )
    (net (code "115") (name "unconnected-(U2D-IO_L49N_3-Pad11)") (class "Default")
      (node (ref "U2") (pin "11") (pinfunction "IO_L49N_3_11") (pintype "bidirectional"))
    )
    (net (code "116") (name "unconnected-(U2D-IO_L49P_3-Pad12)") (class "Default")
      (node (ref "U2") (pin "12") (pinfunction "IO_L49P_3_12") (pintype "bidirectional"))
    )
  )
)
